# 07_USB.net
KiCad netlist of a schematic drawn in Altium Designer
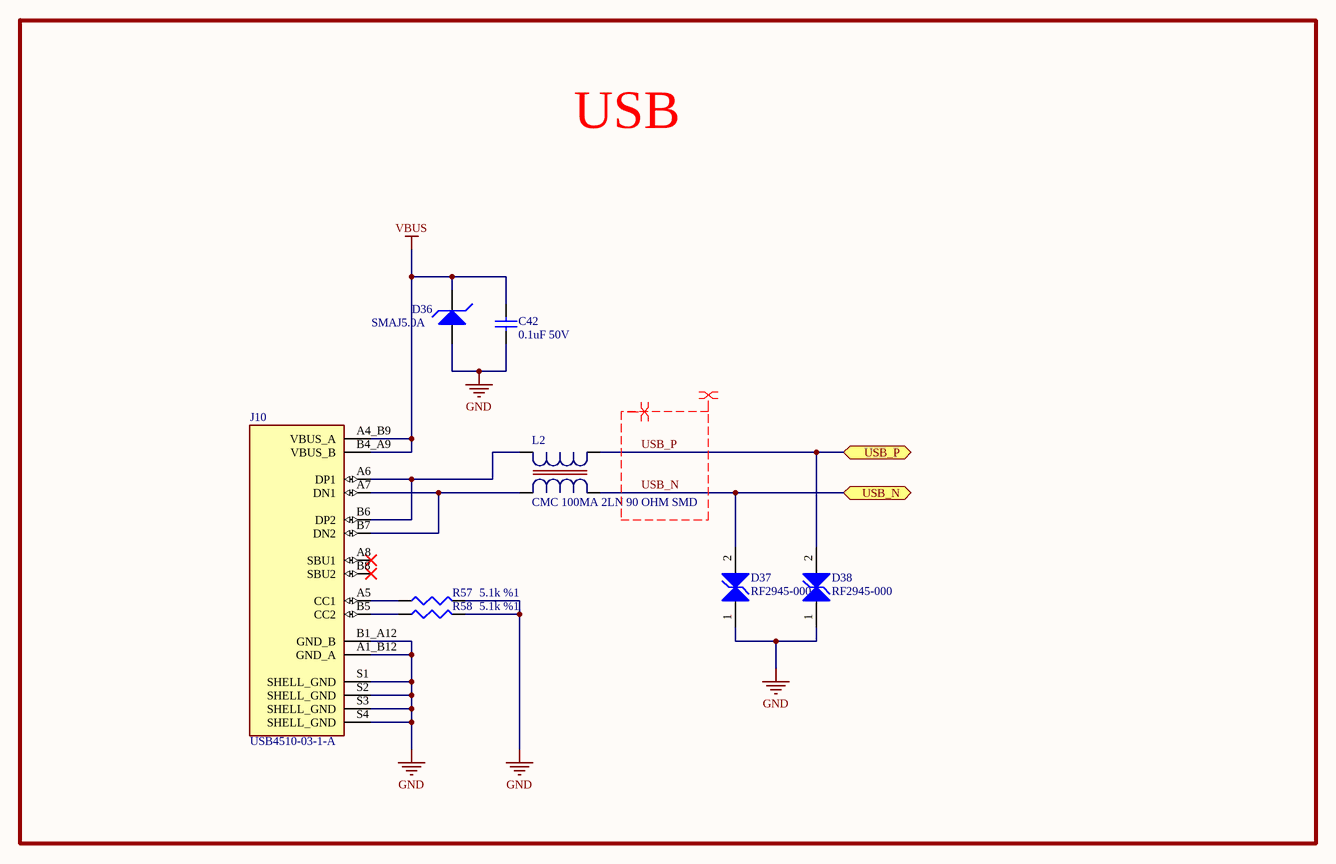
[diagram p0: 07_USB.SchDoc]

(export (version "E")
  (design (tool "Eeschema 10.0.6"))
  (components
    (comp (ref "C42")
      (value "0.1uF 50V")
      (footprint "SMC0402")
      (description "0.1 µF ±10% 50V Ceramic Capacitor X7R 0402 (1005 Metric)")
      (fields
        (field (name "MANUFACTURER PART NUMBER") "GCM155R71H104KE02J")
        (field (name "Comment") "CAP CER 0.1UF 50V X7R 0402")
      )
      (libsource (lib "HW_ADHERENT_LANECTRL_R1") (part "CAP0402_0.1UF_50V_1"))
    )
    (comp (ref "D36")
      (value "SMAJ5.0A")
      (footprint "SMAJ5.0A")
      (description "9.2V Clamp 43.5A Ipp Tvs Diode Surface Mount DO-214AC (SMA)")
      (fields (field (name "MANUFACTURER") "Littelfuse Inc."))
      (libsource (lib "HW_ADHERENT_LANECTRL_R1") (part "SMAJ5.0A"))
    )
    (comp (ref "D37")
      (value "RF2945-000")
      (footprint "Littelfuse_SESD0402_MFG")
      (description "10V (Typ) Clamp 2A (8/20µs) Ipp Tvs Diode Surface Mount 0402")
      (fields
        (field (name "MANUFACTURER PART NUMBER") "SESD0402X1BN-0010-098")
        (field (name "Comment") "TVS DIODE 7VWM 10VC 0402")
      )
      (libsource (lib "HW_ADHERENT_LANECTRL_R1") (part "RF2945-000"))
    )
    (comp (ref "D38")
      (value "RF2945-000")
      (footprint "Littelfuse_SESD0402_MFG")
      (description "10V (Typ) Clamp 2A (8/20µs) Ipp Tvs Diode Surface Mount 0402")
      (fields
        (field (name "MANUFACTURER PART NUMBER") "SESD0402X1BN-0010-098")
        (field (name "Comment") "TVS DIODE 7VWM 10VC 0402")
      )
      (libsource (lib "HW_ADHERENT_LANECTRL_R1") (part "RF2945-000"))
    )
    (comp (ref "J10")
      (value "USB C REC 16P 3U\" MID MNT 1.6MM")
      (footprint "GCT_USB4510-03-1-A_REVA")
      (fields (field (name "MANUFACTURER PART NUMBER") "USB4510-03-1-A"))
      (libsource (lib "HW_ADHERENT_LANECTRL_R1") (part "USB4510-03-1-A_REVA"))
    )
    (comp (ref "L2")
      (value "CMC 100MA 2LN 90 OHM SMD")
      (footprint "IND_MCZ1210AH_TDK")
      (description "2 Line Common Mode Choke Surface Mount 90 Ohms @ 100 MHz 100mA DCR 1.75Ohm")
      (fields
        (field (name "MANUFACTURER PART NUMBER") "MCZ1210AH900L2TA0G")
        (field (name "LCSC MANUFACTURER PART NUMBER") "MCZ1210AH900L2TD0G")
      )
      (libsource (lib "HW_ADHERENT_LANECTRL_R1") (part "MCZ1210AH900L2T"))
    )
    (comp (ref "R57")
      (value "5.1k %1")
      (footprint "SMR0402")
      (description "5.1 kOhms ±1% 0.063W, 1/16W Chip Resistor 0402 (1005 Metric) Automotive AEC-Q200 Thick Film")
      (fields
        (field (name "MANUFACTURER PART NUMBER") "CRCW04025K10FKED")
        (field (name "Comment") "RES SMD 5.1K OHM 1% 1/16W 0402")
      )
      (libsource (lib "HW_ADHERENT_LANECTRL_R1") (part "RES0402_5.1K_%1"))
    )
    (comp (ref "R58")
      (value "5.1k %1")
      (footprint "SMR0402")
      (description "5.1 kOhms ±1% 0.063W, 1/16W Chip Resistor 0402 (1005 Metric) Automotive AEC-Q200 Thick Film")
      (fields
        (field (name "MANUFACTURER PART NUMBER") "CRCW04025K10FKED")
        (field (name "Comment") "RES SMD 5.1K OHM 1% 1/16W 0402")
      )
      (libsource (lib "HW_ADHERENT_LANECTRL_R1") (part "RES0402_5.1K_%1"))
    )
  )
  (nets
    (net (code "1") (name "/USB_N") (class "Default")
      (node (ref "D37") (pin "2") (pinfunction "2_2") (pintype "passive"))
      (node (ref "L2") (pin "3") (pinfunction "4_3") (pintype "passive"))
    )
    (net (code "2") (name "/USB_P") (class "Default")
      (node (ref "D38") (pin "2") (pinfunction "2_2") (pintype "passive"))
      (node (ref "L2") (pin "4") (pinfunction "4_4") (pintype "passive"))
    )
    (net (code "3") (name "GND") (class "Default")
      (node (ref "C42") (pin "1") (pinfunction "1_1") (pintype "passive"))
      (node (ref "D36") (pin "1") (pinfunction "A_1") (pintype "passive"))
      (node (ref "D37") (pin "1") (pinfunction "1_1") (pintype "passive"))
      (node (ref "D38") (pin "1") (pinfunction "1_1") (pintype "passive"))
      (node (ref "J10") (pin "A1_B12") (pinfunction "GND_A_A1_B12") (pintype "power_in"))
      (node (ref "J10") (pin "B1_A12") (pinfunction "GND_B_B1_A12") (pintype "power_in"))
      (node (ref "J10") (pin "S1") (pinfunction "SHELL_GND_S1") (pintype "power_in"))
      (node (ref "J10") (pin "S2") (pinfunction "SHELL_GND_S2") (pintype "power_in"))
      (node (ref "J10") (pin "S3") (pinfunction "SHELL_GND_S3") (pintype "power_in"))
      (node (ref "J10") (pin "S4") (pinfunction "SHELL_GND_S4") (pintype "power_in"))
      (node (ref "R57") (pin "2") (pinfunction "2_2") (pintype "passive"))
      (node (ref "R58") (pin "2") (pinfunction "2_2") (pintype "passive"))
    )
    (net (code "4") (name "Net-(J10-CC1)") (class "Default")
      (node (ref "J10") (pin "A5") (pinfunction "CC1_A5") (pintype "bidirectional"))
      (node (ref "R57") (pin "1") (pinfunction "1_1") (pintype "passive"))
    )
    (net (code "5") (name "Net-(J10-CC2)") (class "Default")
      (node (ref "J10") (pin "B5") (pinfunction "CC2_B5") (pintype "bidirectional"))
      (node (ref "R58") (pin "1") (pinfunction "1_1") (pintype "passive"))
    )
    (net (code "6") (name "Net-(J10-DN1)") (class "Default")
      (node (ref "J10") (pin "A7") (pinfunction "DN1_A7") (pintype "bidirectional"))
      (node (ref "J10") (pin "B7") (pinfunction "DN2_B7") (pintype "bidirectional"))
      (node (ref "L2") (pin "2") (pinfunction "2_2") (pintype "passive"))
    )
    (net (code "7") (name "Net-(J10-DP1)") (class "Default")
      (node (ref "J10") (pin "A6") (pinfunction "DP1_A6") (pintype "bidirectional"))
      (node (ref "J10") (pin "B6") (pinfunction "DP2_B6") (pintype "bidirectional"))
      (node (ref "L2") (pin "1") (pinfunction "1_1") (pintype "passive"))
    )
    (net (code "8") (name "VBUS") (class "Default")
      (node (ref "C42") (pin "2") (pinfunction "2_2") (pintype "passive"))
      (node (ref "D36") (pin "2") (pinfunction "K_2") (pintype "passive"))
      (node (ref "J10") (pin "A4_B9") (pinfunction "VBUS_A_A4_B9") (pintype "power_in"))
      (node (ref "J10") (pin "B4_A9") (pinfunction "VBUS_B_B4_A9") (pintype "power_in"))
    )
    (net (code "9") (name "unconnected-(J10-SBU1-PadA8)") (class "Default")
      (node (ref "J10") (pin "A8") (pinfunction "SBU1_A8") (pintype "bidirectional+no_connect"))
    )
    (net (code "10") (name "unconnected-(J10-SBU2-PadB8)") (class "Default")
      (node (ref "J10") (pin "B8") (pinfunction "SBU2_B8") (pintype "bidirectional+no_connect"))
    )
  )
)
